# Sensors.net
KiCad netlist of a schematic drawn in Altium Designer
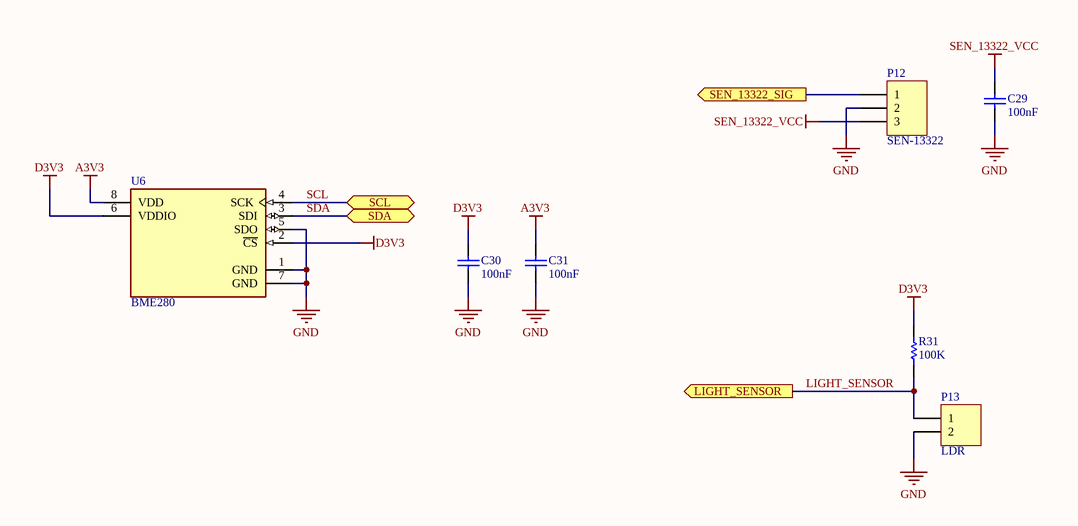
[diagram p0: Sensors.SchDoc]

(export (version "E")
  (design (tool "Eeschema 10.0.6"))
  (components
    (comp (ref "C29")
      (value "100nF")
      (footprint "CAP0603")
      (description "Capacitor")
      (fields (field (name "PUBLISHER") "Altium Limited"))
      (libsource (lib "Taiv") (part "Capacitor"))
    )
    (comp (ref "C30")
      (value "100nF")
      (footprint "CAP0603")
      (description "Capacitor")
      (fields (field (name "PUBLISHER") "Altium Limited"))
      (libsource (lib "Taiv") (part "Capacitor"))
    )
    (comp (ref "C31")
      (value "100nF")
      (footprint "CAP0603")
      (description "Capacitor")
      (fields (field (name "PUBLISHER") "Altium Limited"))
      (libsource (lib "Taiv") (part "Capacitor"))
    )
    (comp (ref "P12")
      (value "SEN-13322")
      (footprint "MOLEX MICROLATCH 3CT")
      (description "Header, 3-Pin")
      (fields (field (name "PUBLISHER") "Altium Limited"))
      (libsource (lib "Taiv") (part "3X1 2.54MM"))
    )
    (comp (ref "P13")
      (value "LDR")
      (footprint "MOLEX MICROLATCH 2CT")
      (description "Header, 2-Pin")
      (fields (field (name "PUBLISHER") "Altium Limited"))
      (libsource (lib "Taiv") (part "2X1 2.54MM"))
    )
    (comp (ref "R31")
      (value "100K")
      (footprint "RES0603")
      (description "Resistor")
      (fields (field (name "PUBLISHER") "Altium Limited"))
      (libsource (lib "Taiv") (part "Resistor"))
    )
    (comp (ref "U6")
      (value "BME280")
      (footprint "BME280")
      (description "SENSOR PRESSURE HUMIDITY TEMP")
      (libsource (lib "Taiv") (part "BME280"))
    )
  )
  (nets
    (net (code "1") (name "/LIGHT_SENSOR") (class "Default")
      (node (ref "P13") (pin "1") (pinfunction "1_1") (pintype "passive"))
      (node (ref "R31") (pin "1") (pinfunction "1_1") (pintype "passive"))
    )
    (net (code "2") (name "/SCL") (class "Default")
      (node (ref "U6") (pin "4") (pinfunction "SCK_4") (pintype "input"))
    )
    (net (code "3") (name "/SDA") (class "Default")
      (node (ref "U6") (pin "3") (pinfunction "SDI_3") (pintype "bidirectional"))
    )
    (net (code "4") (name "/SEN_13322_SIG") (class "Default")
      (node (ref "P12") (pin "1") (pinfunction "1_1") (pintype "passive"))
    )
    (net (code "5") (name "A3V3") (class "Default")
      (node (ref "C31") (pin "2") (pinfunction "2_2") (pintype "passive"))
      (node (ref "U6") (pin "8") (pinfunction "VDD_8") (pintype "power_in"))
    )
    (net (code "6") (name "D3V3") (class "Default")
      (node (ref "C30") (pin "2") (pinfunction "2_2") (pintype "passive"))
      (node (ref "R31") (pin "2") (pinfunction "2_2") (pintype "passive"))
      (node (ref "U6") (pin "2") (pinfunction "~{CS}_2") (pintype "input"))
      (node (ref "U6") (pin "6") (pinfunction "VDDIO_6") (pintype "power_in"))
    )
    (net (code "7") (name "GND") (class "Default")
      (node (ref "C29") (pin "1") (pinfunction "1_1") (pintype "passive"))
      (node (ref "C30") (pin "1") (pinfunction "1_1") (pintype "passive"))
      (node (ref "C31") (pin "1") (pinfunction "1_1") (pintype "passive"))
      (node (ref "P12") (pin "2") (pinfunction "2_2") (pintype "passive"))
      (node (ref "P13") (pin "2") (pinfunction "2_2") (pintype "passive"))
      (node (ref "U6") (pin "1") (pinfunction "GND_1") (pintype "power_in"))
      (node (ref "U6") (pin "5") (pinfunction "SDO_5") (pintype "bidirectional"))
      (node (ref "U6") (pin "7") (pinfunction "GND_7") (pintype "power_in"))
    )
    (net (code "8") (name "SEN_13322_VCC") (class "Default")
      (node (ref "C29") (pin "2") (pinfunction "2_2") (pintype "passive"))
      (node (ref "P12") (pin "3") (pinfunction "3_3") (pintype "passive"))
    )
  )
)
